# XTree.net
KiCad netlist of a schematic drawn in EAGLE
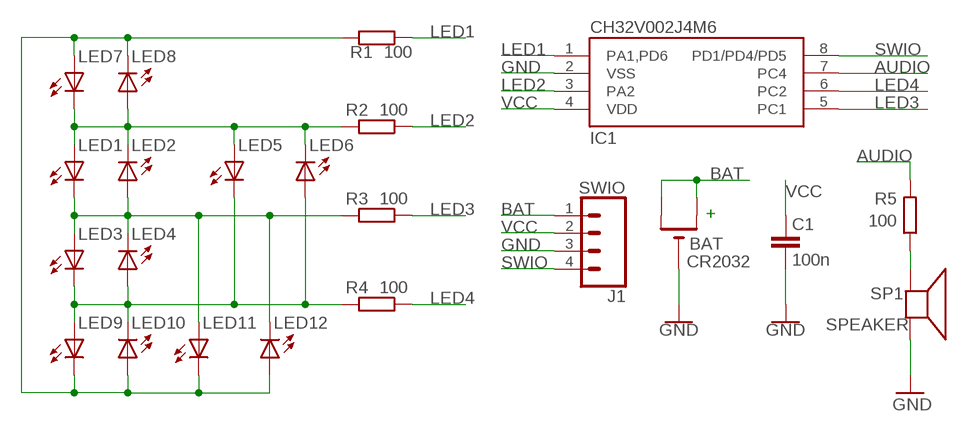
[diagram p0: schematic, sheet 1]

(export (version "E")
  (design (tool "Eeschema 10.0.6"))
  (components
    (comp (ref "BAT")
      (value "CR2032")
      (footprint "eagle-import:CR2032-SMD")
      (libsource (lib "eagle-import") (part "CR2032SMT"))
    )
    (comp (ref "C1")
      (value "100n")
      (footprint "eagle-import:C1206K")
      (libsource (lib "eagle-import") (part "C-EUC1206K"))
    )
    (comp (ref "IC1")
      (value "CH32V002J4M6")
      (footprint "eagle-import:SOP8")
      (libsource (lib "eagle-import") (part "CH32V003J4M6"))
    )
    (comp (ref "J1")
      (value "SWIO")
      (footprint "eagle-import:1X04_SMD_LONG")
      (libsource (lib "eagle-import") (part "CONN_04SMD_LONG"))
    )
    (comp (ref "LED1")
      (value "LED5MM")
      (footprint "eagle-import:LED5MM")
      (libsource (lib "eagle-import") (part "LED5MM"))
    )
    (comp (ref "LED2")
      (value "LED5MM")
      (footprint "eagle-import:LED5MM")
      (libsource (lib "eagle-import") (part "LED5MM"))
    )
    (comp (ref "LED3")
      (value "LED5MM")
      (footprint "eagle-import:LED5MM")
      (libsource (lib "eagle-import") (part "LED5MM"))
    )
    (comp (ref "LED4")
      (value "LED5MM")
      (footprint "eagle-import:LED5MM")
      (libsource (lib "eagle-import") (part "LED5MM"))
    )
    (comp (ref "LED5")
      (value "LED5MM")
      (footprint "eagle-import:LED5MM")
      (libsource (lib "eagle-import") (part "LED5MM"))
    )
    (comp (ref "LED6")
      (value "LED5MM")
      (footprint "eagle-import:LED5MM")
      (libsource (lib "eagle-import") (part "LED5MM"))
    )
    (comp (ref "LED7")
      (value "LED5MM")
      (footprint "eagle-import:LED5MM")
      (libsource (lib "eagle-import") (part "LED5MM"))
    )
    (comp (ref "LED8")
      (value "LED5MM")
      (footprint "eagle-import:LED5MM")
      (libsource (lib "eagle-import") (part "LED5MM"))
    )
    (comp (ref "LED9")
      (value "LED5MM")
      (footprint "eagle-import:LED5MM")
      (libsource (lib "eagle-import") (part "LED5MM"))
    )
    (comp (ref "LED10")
      (value "LED5MM")
      (footprint "eagle-import:LED5MM")
      (libsource (lib "eagle-import") (part "LED5MM"))
    )
    (comp (ref "LED11")
      (value "LED5MM")
      (footprint "eagle-import:LED5MM")
      (libsource (lib "eagle-import") (part "LED5MM"))
    )
    (comp (ref "LED12")
      (value "LED5MM")
      (footprint "eagle-import:LED5MM")
      (libsource (lib "eagle-import") (part "LED5MM"))
    )
    (comp (ref "R1")
      (value "100")
      (footprint "eagle-import:M1206")
      (libsource (lib "eagle-import") (part "R-EU_M1206"))
    )
    (comp (ref "R2")
      (value "100")
      (footprint "eagle-import:M1206")
      (libsource (lib "eagle-import") (part "R-EU_M1206"))
    )
    (comp (ref "R3")
      (value "100")
      (footprint "eagle-import:M1206")
      (libsource (lib "eagle-import") (part "R-EU_M1206"))
    )
    (comp (ref "R4")
      (value "100")
      (footprint "eagle-import:M1206")
      (libsource (lib "eagle-import") (part "R-EU_M1206"))
    )
    (comp (ref "R5")
      (value "100")
      (footprint "eagle-import:M1206")
      (libsource (lib "eagle-import") (part "R-EU_M1206"))
    )
    (comp (ref "SP1")
      (value "SPEAKER")
      (footprint "eagle-import:AL60P_3")
      (libsource (lib "eagle-import") (part "SPEAKERAL60P_3"))
    )
  )
  (nets
    (net (code "1") (name "/AUDIO") (class "Default")
      (node (ref "IC1") (pin "7") (pinfunction "PC4_7") (pintype "bidirectional"))
      (node (ref "R5") (pin "2") (pinfunction "2_2") (pintype "passive"))
    )
    (net (code "2") (name "/BAT") (class "Default")
      (node (ref "BAT") (pin "+$1") (pinfunction "+_+$1") (pintype "passive"))
      (node (ref "BAT") (pin "+$2") (pinfunction "+1_+$2") (pintype "passive"))
      (node (ref "J1") (pin "1") (pinfunction "1_1") (pintype "passive"))
    )
    (net (code "3") (name "/LED1") (class "Default")
      (node (ref "IC1") (pin "1") (pinfunction "PA1,PD6_1") (pintype "bidirectional"))
      (node (ref "R1") (pin "1") (pinfunction "1_1") (pintype "passive"))
    )
    (net (code "4") (name "/LED2") (class "Default")
      (node (ref "IC1") (pin "3") (pinfunction "PA2_3") (pintype "bidirectional"))
      (node (ref "R2") (pin "1") (pinfunction "1_1") (pintype "passive"))
    )
    (net (code "5") (name "/LED3") (class "Default")
      (node (ref "IC1") (pin "5") (pinfunction "PC1_5") (pintype "bidirectional"))
      (node (ref "R3") (pin "1") (pinfunction "1_1") (pintype "passive"))
    )
    (net (code "6") (name "/LED4") (class "Default")
      (node (ref "IC1") (pin "6") (pinfunction "PC2_6") (pintype "bidirectional"))
      (node (ref "R4") (pin "1") (pinfunction "1_1") (pintype "passive"))
    )
    (net (code "7") (name "/SWIO") (class "Default")
      (node (ref "IC1") (pin "8") (pinfunction "PD1/PD4/PD5_8") (pintype "bidirectional"))
      (node (ref "J1") (pin "4") (pinfunction "4_4") (pintype "passive"))
    )
    (net (code "8") (name "/VCC") (class "Default")
      (node (ref "C1") (pin "1") (pinfunction "1_1") (pintype "passive"))
      (node (ref "IC1") (pin "4") (pinfunction "VDD_4") (pintype "power_in"))
      (node (ref "J1") (pin "2") (pinfunction "2_2") (pintype "passive"))
    )
    (net (code "9") (name "GND") (class "Default")
      (node (ref "BAT") (pin "-") (pinfunction "-_-") (pintype "passive"))
      (node (ref "C1") (pin "2") (pinfunction "2_2") (pintype "passive"))
      (node (ref "IC1") (pin "2") (pinfunction "VSS_2") (pintype "power_in"))
      (node (ref "J1") (pin "3") (pinfunction "3_3") (pintype "passive"))
      (node (ref "SP1") (pin "2") (pinfunction "-_2") (pintype "passive"))
    )
    (net (code "10") (name "Net-(LED1-C)") (class "Default")
      (node (ref "LED1") (pin "K") (pinfunction "C_K") (pintype "passive"))
      (node (ref "LED11") (pin "A") (pinfunction "A_A") (pintype "passive"))
      (node (ref "LED12") (pin "K") (pinfunction "C_K") (pintype "passive"))
      (node (ref "LED2") (pin "A") (pinfunction "A_A") (pintype "passive"))
      (node (ref "LED3") (pin "A") (pinfunction "A_A") (pintype "passive"))
      (node (ref "LED4") (pin "K") (pinfunction "C_K") (pintype "passive"))
      (node (ref "R3") (pin "2") (pinfunction "2_2") (pintype "passive"))
    )
    (net (code "11") (name "Net-(LED2-C)") (class "Default")
      (node (ref "LED1") (pin "A") (pinfunction "A_A") (pintype "passive"))
      (node (ref "LED2") (pin "K") (pinfunction "C_K") (pintype "passive"))
      (node (ref "LED5") (pin "A") (pinfunction "A_A") (pintype "passive"))
      (node (ref "LED6") (pin "K") (pinfunction "C_K") (pintype "passive"))
      (node (ref "LED7") (pin "K") (pinfunction "C_K") (pintype "passive"))
      (node (ref "LED8") (pin "A") (pinfunction "A_A") (pintype "passive"))
      (node (ref "R2") (pin "2") (pinfunction "2_2") (pintype "passive"))
    )
    (net (code "12") (name "Net-(LED10-C)") (class "Default")
      (node (ref "LED10") (pin "K") (pinfunction "C_K") (pintype "passive"))
      (node (ref "LED3") (pin "K") (pinfunction "C_K") (pintype "passive"))
      (node (ref "LED4") (pin "A") (pinfunction "A_A") (pintype "passive"))
      (node (ref "LED5") (pin "K") (pinfunction "C_K") (pintype "passive"))
      (node (ref "LED6") (pin "A") (pinfunction "A_A") (pintype "passive"))
      (node (ref "LED9") (pin "A") (pinfunction "A_A") (pintype "passive"))
      (node (ref "R4") (pin "2") (pinfunction "2_2") (pintype "passive"))
    )
    (net (code "13") (name "Net-(LED11-C)") (class "Default")
      (node (ref "LED10") (pin "A") (pinfunction "A_A") (pintype "passive"))
      (node (ref "LED11") (pin "K") (pinfunction "C_K") (pintype "passive"))
      (node (ref "LED12") (pin "A") (pinfunction "A_A") (pintype "passive"))
      (node (ref "LED7") (pin "A") (pinfunction "A_A") (pintype "passive"))
      (node (ref "LED8") (pin "K") (pinfunction "C_K") (pintype "passive"))
      (node (ref "LED9") (pin "K") (pinfunction "C_K") (pintype "passive"))
      (node (ref "R1") (pin "2") (pinfunction "2_2") (pintype "passive"))
    )
    (net (code "14") (name "Net-(SP1-+)") (class "Default")
      (node (ref "R5") (pin "1") (pinfunction "1_1") (pintype "passive"))
      (node (ref "SP1") (pin "1") (pinfunction "+_1") (pintype "passive"))
    )
  )
)
